# SimpleServo.net
KiCad netlist of a schematic drawn in EAGLE
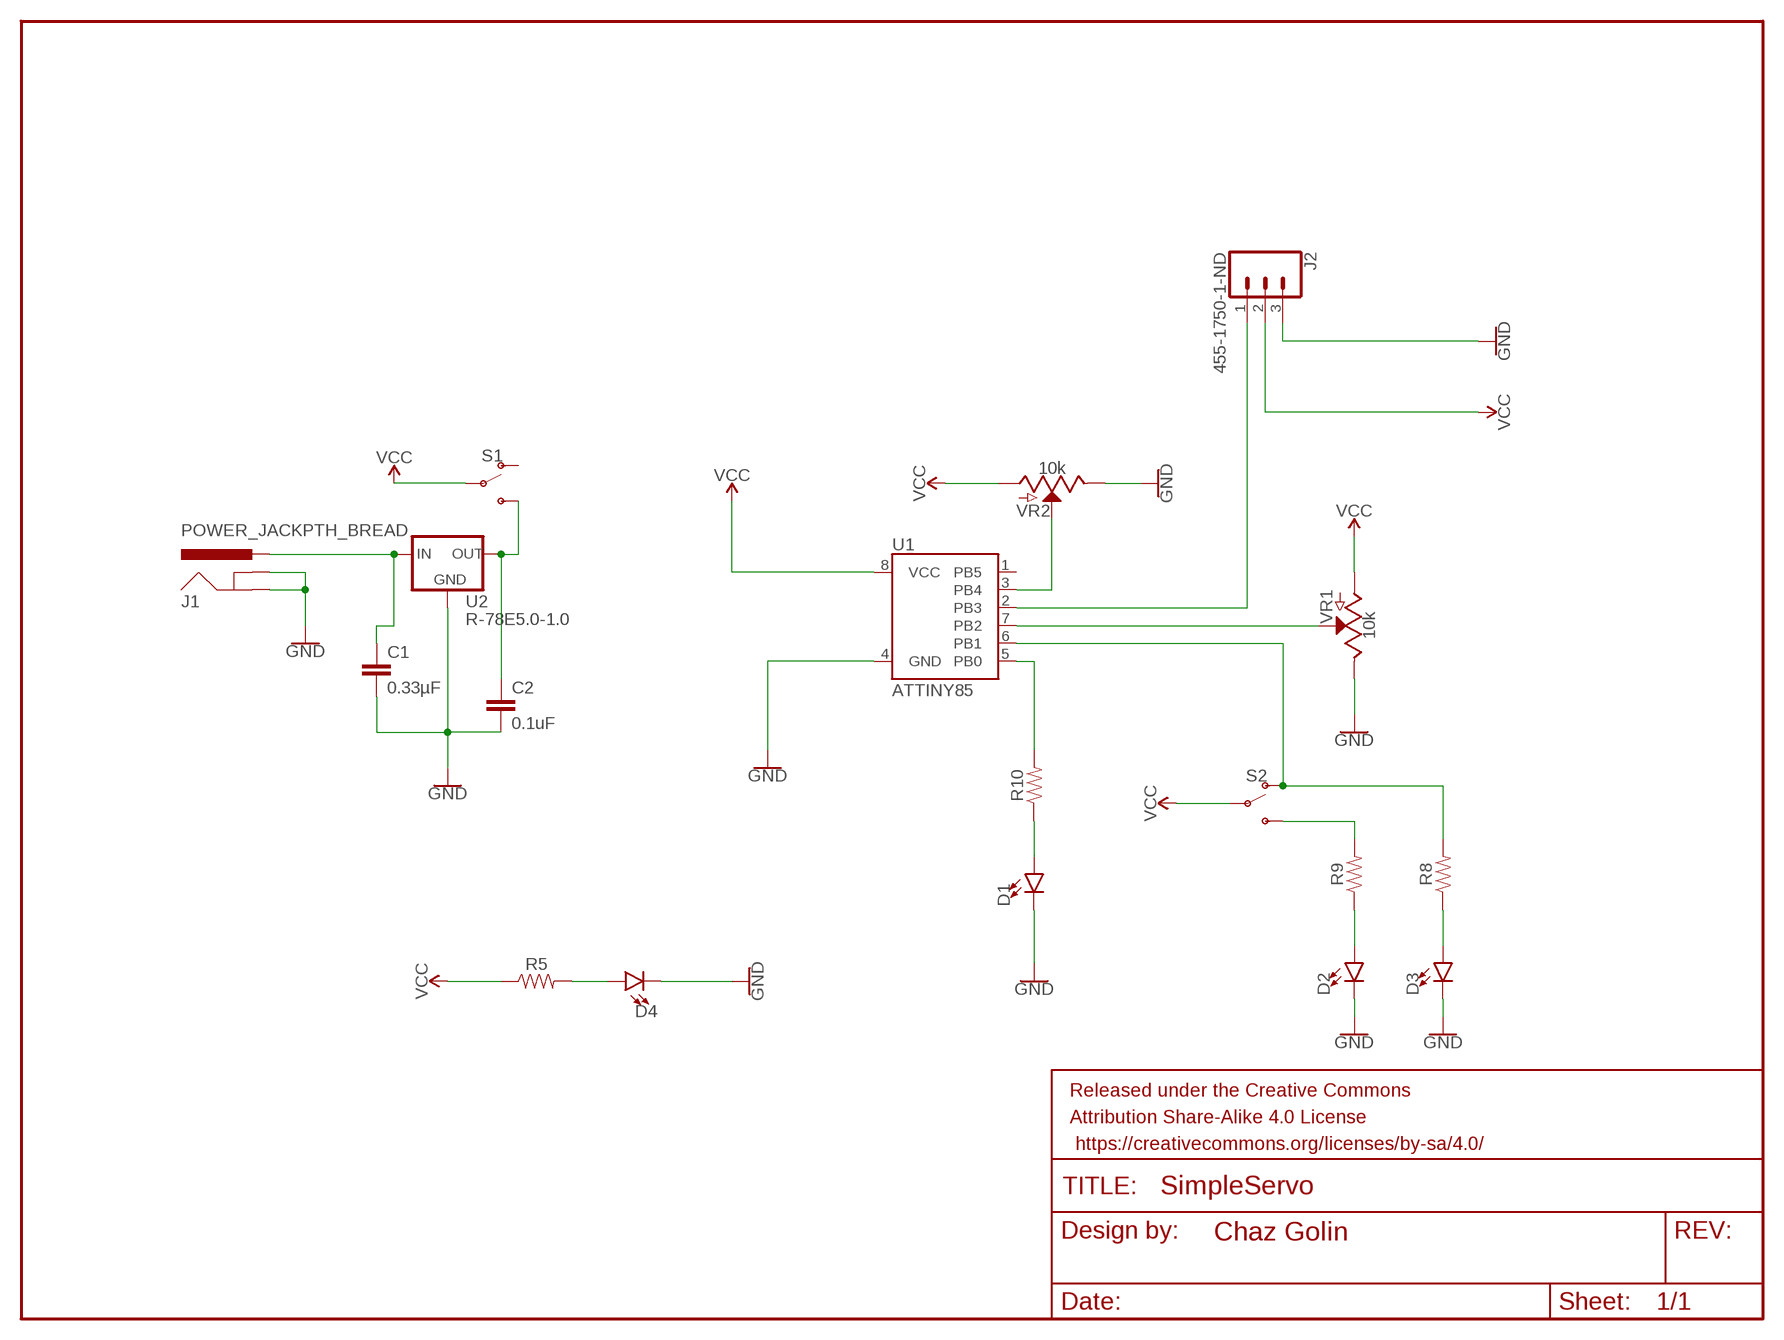
[diagram p0: schematic, sheet 1]

(export (version "E")
  (design (tool "Eeschema 10.0.6"))
  (components
    (comp (ref "C1")
      (value "0.33µF")
      (footprint "eagle-import:0805")
      (libsource (lib "eagle-import") (part "0.33UF/330NF-0805-50V-10%"))
    )
    (comp (ref "C2")
      (value "0.1uF")
      (footprint "eagle-import:0402")
      (libsource (lib "eagle-import") (part "0.1UF-0402-6.3V-10%-X7R"))
    )
    (comp (ref "D1")
      (value "LED3MM")
      (footprint "eagle-import:LED_3MM")
      (libsource (lib "eagle-import") (part "LED3MM"))
    )
    (comp (ref "D2")
      (value "LED3MM")
      (footprint "eagle-import:LED_3MM")
      (libsource (lib "eagle-import") (part "LED3MM"))
    )
    (comp (ref "D3")
      (value "LED3MM")
      (footprint "eagle-import:LED_3MM")
      (libsource (lib "eagle-import") (part "LED3MM"))
    )
    (comp (ref "D4")
      (value "LED3MM")
      (footprint "eagle-import:LED_3MM")
      (libsource (lib "eagle-import") (part "LED3MM"))
    )
    (comp (ref "FRAME1")
      (value "FRAME-LETTER")
      (footprint "eagle-import:CREATIVE_COMMONS")
      (fields (field (name "DESIGNER") "Chaz Golin"))
      (libsource (lib "eagle-import") (part "FRAME-LETTER"))
    )
    (comp (ref "J1")
      (value "POWER_JACKPTH_BREAD")
      (footprint "eagle-import:POWER_JACK_PTH_BREAD")
      (libsource (lib "eagle-import") (part "POWER_JACKPTH_BREAD"))
    )
    (comp (ref "J2")
      (value "455-1750-1-ND")
      (footprint "eagle-import:1X03")
      (libsource (lib "eagle-import") (part "CONN_03"))
    )
    (comp (ref "R5")
      (value "RESISTORAXIAL-0.3")
      (footprint "eagle-import:AXIAL-0.3")
      (libsource (lib "eagle-import") (part "RESISTORAXIAL-0.3"))
    )
    (comp (ref "R8")
      (value "RESISTORAXIAL-0.3")
      (footprint "eagle-import:AXIAL-0.3")
      (libsource (lib "eagle-import") (part "RESISTORAXIAL-0.3"))
    )
    (comp (ref "R9")
      (value "RESISTORAXIAL-0.3")
      (footprint "eagle-import:AXIAL-0.3")
      (libsource (lib "eagle-import") (part "RESISTORAXIAL-0.3"))
    )
    (comp (ref "R10")
      (value "RESISTORAXIAL-0.3")
      (footprint "eagle-import:AXIAL-0.3")
      (libsource (lib "eagle-import") (part "RESISTORAXIAL-0.3"))
    )
    (comp (ref "S1")
      (value "SWITCH-SPDT-PTH-11.6X4.0MM")
      (footprint "eagle-import:SWITCH_SPDT_PTH_11.6X4.0MM")
      (libsource (lib "eagle-import") (part "SWITCH-SPDT-PTH-11.6X4.0MM"))
    )
    (comp (ref "S2")
      (value "SWITCH-SPDT-PTH-11.6X4.0MM")
      (footprint "eagle-import:SWITCH_SPDT_PTH_11.6X4.0MM")
      (libsource (lib "eagle-import") (part "SWITCH-SPDT-PTH-11.6X4.0MM"))
    )
    (comp (ref "U1")
      (value "ATTINY85")
      (footprint "eagle-import:ATTINY85")
      (libsource (lib "eagle-import") (part "ATTINY85"))
    )
    (comp (ref "U2")
      (value "R-78E5.0-1.0")
      (footprint "eagle-import:DC-DC_CONVERTER_78XX")
      (libsource (lib "eagle-import") (part "R-78E5.0-1.0"))
    )
    (comp (ref "VR1")
      (value "10k")
      (footprint "eagle-import:POT-PTH-ALPS")
      (libsource (lib "eagle-import") (part "POTENTIOMETER-PTH-9MM-1/20W-20%"))
    )
    (comp (ref "VR2")
      (value "10k")
      (footprint "eagle-import:POT-PTH-ALPS")
      (libsource (lib "eagle-import") (part "POTENTIOMETER-PTH-9MM-1/20W-20%"))
    )
  )
  (nets
    (net (code "1") (name "GND") (class "Default")
      (node (ref "C1") (pin "2") (pinfunction "2_2") (pintype "passive"))
      (node (ref "C2") (pin "2") (pinfunction "2_2") (pintype "passive"))
      (node (ref "D1") (pin "K") (pinfunction "C_K") (pintype "passive"))
      (node (ref "D2") (pin "K") (pinfunction "C_K") (pintype "passive"))
      (node (ref "D3") (pin "K") (pinfunction "C_K") (pintype "passive"))
      (node (ref "D4") (pin "K") (pinfunction "C_K") (pintype "passive"))
      (node (ref "J1") (pin "GND") (pinfunction "GND_GND") (pintype "bidirectional"))
      (node (ref "J1") (pin "GNDBREAK") (pinfunction "GNDBREAK_GNDBREAK") (pintype "bidirectional"))
      (node (ref "J2") (pin "3") (pinfunction "3_3") (pintype "passive"))
      (node (ref "U1") (pin "4") (pinfunction "GND_4") (pintype "bidirectional"))
      (node (ref "U2") (pin "GND") (pinfunction "GND_GND") (pintype "input"))
      (node (ref "VR1") (pin "P$1") (pinfunction "E_P$1") (pintype "passive"))
      (node (ref "VR2") (pin "P$1") (pinfunction "E_P$1") (pintype "passive"))
    )
    (net (code "2") (name "Net-(R5-2)") (class "Default")
      (node (ref "D4") (pin "A") (pinfunction "A_A") (pintype "passive"))
      (node (ref "R5") (pin "P$2") (pinfunction "2_P$2") (pintype "passive"))
    )
    (net (code "3") (name "Net-(R8-1)") (class "Default")
      (node (ref "D3") (pin "A") (pinfunction "A_A") (pintype "passive"))
      (node (ref "R8") (pin "P$1") (pinfunction "1_P$1") (pintype "passive"))
    )
    (net (code "4") (name "Net-(R8-2)") (class "Default")
      (node (ref "R8") (pin "P$2") (pinfunction "2_P$2") (pintype "passive"))
      (node (ref "S2") (pin "1") (pinfunction "O_1") (pintype "passive"))
      (node (ref "U1") (pin "6") (pinfunction "PB1_6") (pintype "bidirectional"))
    )
    (net (code "5") (name "Net-(R9-1)") (class "Default")
      (node (ref "D2") (pin "A") (pinfunction "A_A") (pintype "passive"))
      (node (ref "R9") (pin "P$1") (pinfunction "1_P$1") (pintype "passive"))
    )
    (net (code "6") (name "Net-(R9-2)") (class "Default")
      (node (ref "R9") (pin "P$2") (pinfunction "2_P$2") (pintype "passive"))
      (node (ref "S2") (pin "3") (pinfunction "S_3") (pintype "passive"))
    )
    (net (code "7") (name "Net-(R10-1)") (class "Default")
      (node (ref "D1") (pin "A") (pinfunction "A_A") (pintype "passive"))
      (node (ref "R10") (pin "P$1") (pinfunction "1_P$1") (pintype "passive"))
    )
    (net (code "8") (name "Net-(R10-2)") (class "Default")
      (node (ref "R10") (pin "P$2") (pinfunction "2_P$2") (pintype "passive"))
      (node (ref "U1") (pin "5") (pinfunction "PB0_5") (pintype "bidirectional"))
    )
    (net (code "9") (name "Net-(S1-S)") (class "Default")
      (node (ref "C2") (pin "1") (pinfunction "1_1") (pintype "passive"))
      (node (ref "S1") (pin "3") (pinfunction "S_3") (pintype "passive"))
      (node (ref "U2") (pin "VOUT") (pinfunction "OUT_VOUT") (pintype "passive"))
    )
    (net (code "10") (name "Net-(U1-PB2)") (class "Default")
      (node (ref "U1") (pin "7") (pinfunction "PB2_7") (pintype "bidirectional"))
      (node (ref "VR1") (pin "P$2") (pinfunction "S_P$2") (pintype "passive"))
    )
    (net (code "11") (name "Net-(U1-PB3)") (class "Default")
      (node (ref "J2") (pin "1") (pinfunction "1_1") (pintype "passive"))
      (node (ref "U1") (pin "2") (pinfunction "PB3_2") (pintype "bidirectional"))
    )
    (net (code "12") (name "Net-(U1-PB4)") (class "Default")
      (node (ref "U1") (pin "3") (pinfunction "PB4_3") (pintype "bidirectional"))
      (node (ref "VR2") (pin "P$2") (pinfunction "S_P$2") (pintype "passive"))
    )
    (net (code "13") (name "Net-(U2-IN)") (class "Default")
      (node (ref "C1") (pin "1") (pinfunction "1_1") (pintype "passive"))
      (node (ref "J1") (pin "PWR") (pinfunction "PWR_PWR") (pintype "bidirectional"))
      (node (ref "U2") (pin "VIN") (pinfunction "IN_VIN") (pintype "input"))
    )
    (net (code "14") (name "VCC") (class "Default")
      (node (ref "J2") (pin "2") (pinfunction "2_2") (pintype "passive"))
      (node (ref "R5") (pin "P$1") (pinfunction "1_P$1") (pintype "passive"))
      (node (ref "S1") (pin "2") (pinfunction "P_2") (pintype "passive"))
      (node (ref "S2") (pin "2") (pinfunction "P_2") (pintype "passive"))
      (node (ref "U1") (pin "8") (pinfunction "VCC_8") (pintype "bidirectional"))
      (node (ref "VR1") (pin "P$3") (pinfunction "A_P$3") (pintype "passive"))
      (node (ref "VR2") (pin "P$3") (pinfunction "A_P$3") (pintype "passive"))
    )
    (net (code "15") (name "unconnected-(S1-O-Pad1)") (class "Default")
      (node (ref "S1") (pin "1") (pinfunction "O_1") (pintype "passive"))
    )
    (net (code "16") (name "unconnected-(U1-PB5-Pad1)") (class "Default")
      (node (ref "U1") (pin "1") (pinfunction "PB5_1") (pintype "bidirectional"))
    )
  )
)
